# HuMem_rev_A.net
KiCad netlist of a schematic drawn in EAGLE
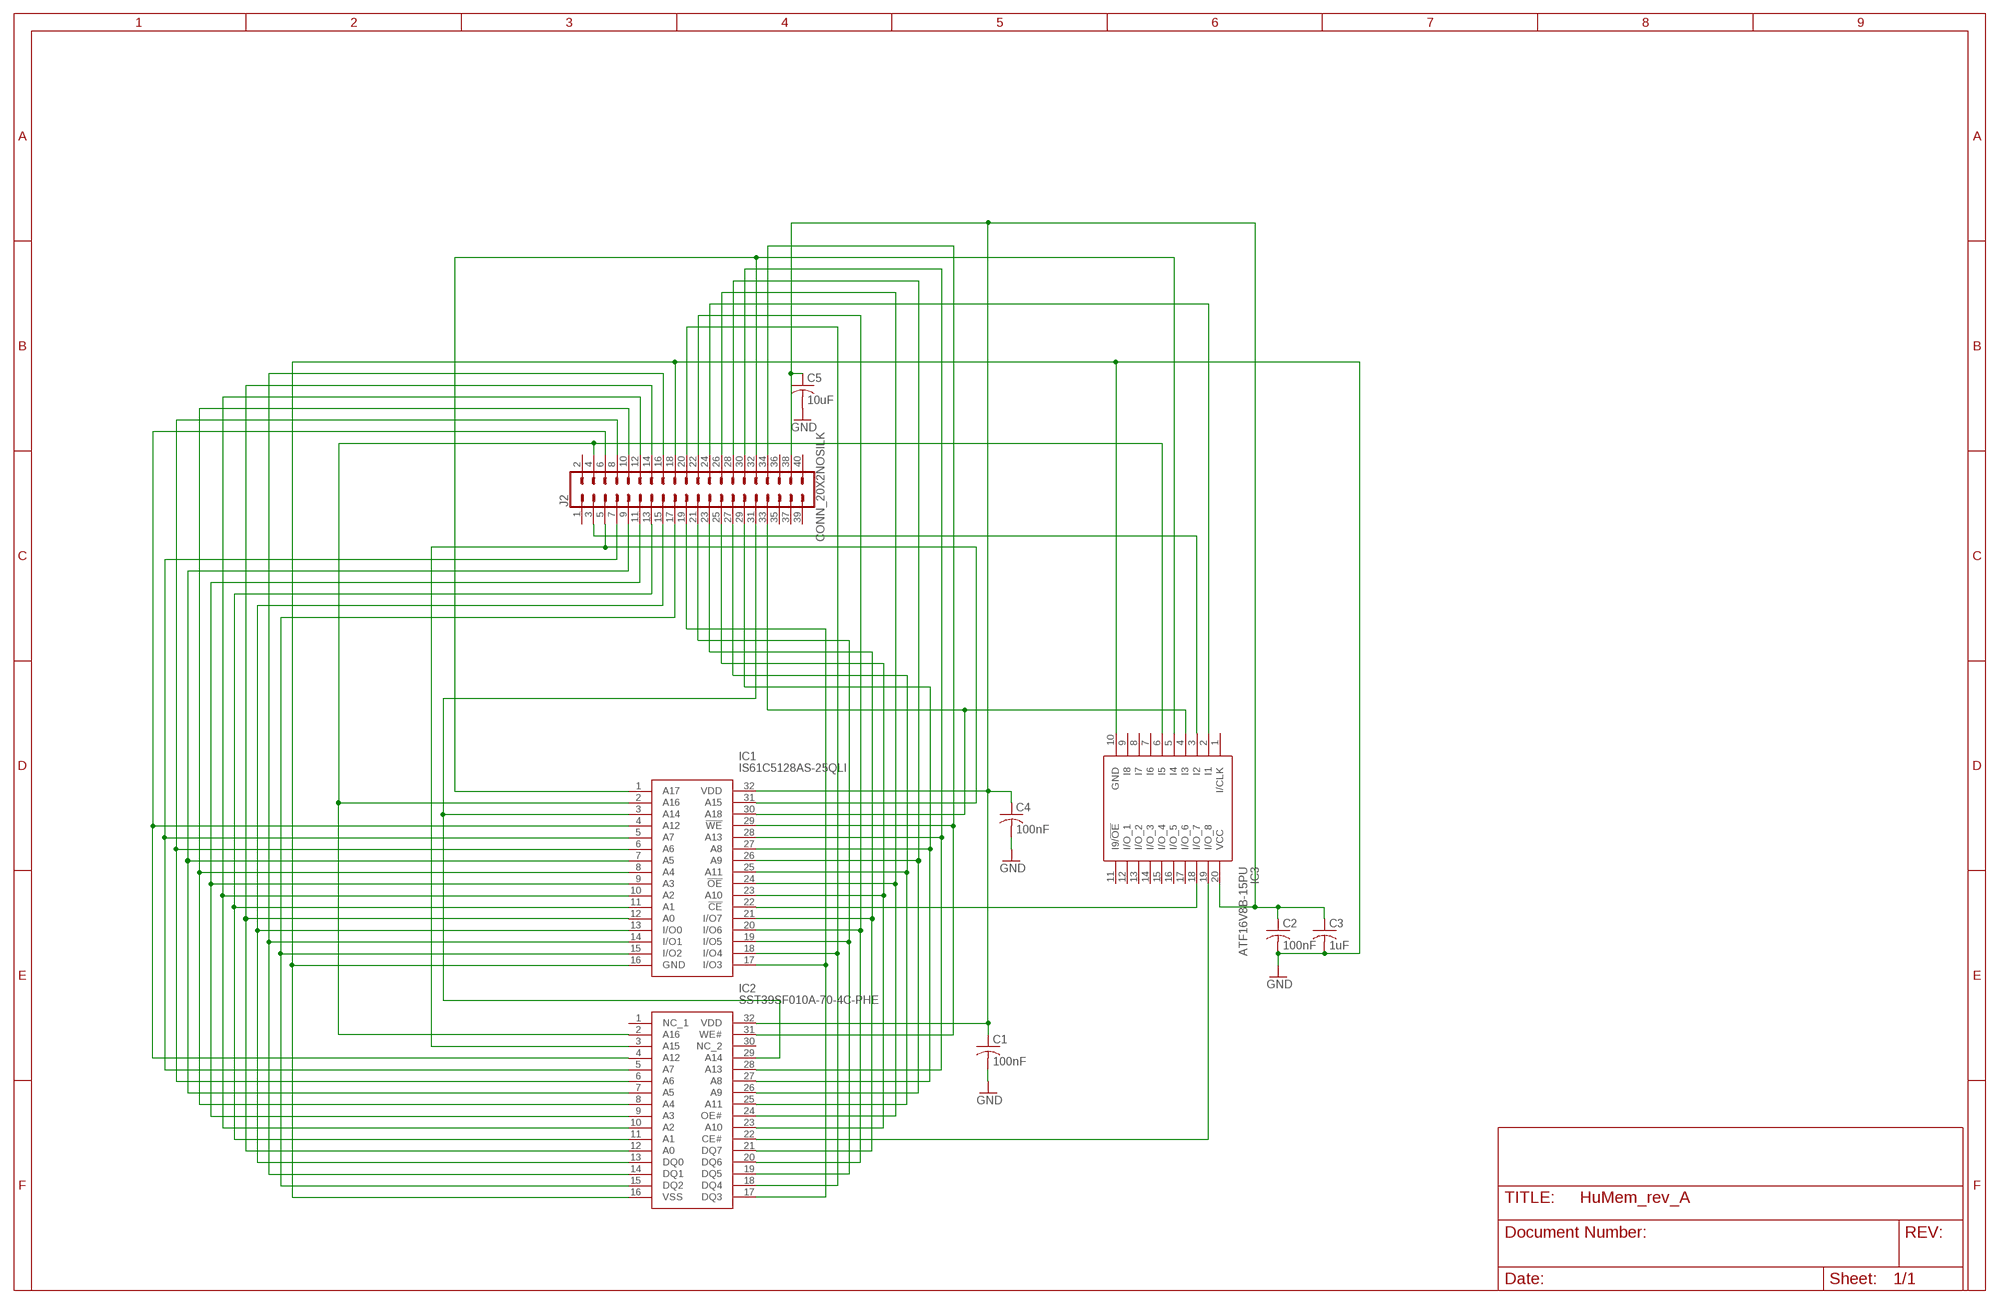
[diagram p0: schematic, sheet 1]

(export (version "E")
  (design (tool "Eeschema 10.0.6"))
  (components
    (comp (ref "C1")
      (value "100nF")
      (footprint "eagle-import:C0603")
      (libsource (lib "eagle-import") (part "C-USC0603"))
    )
    (comp (ref "C2")
      (value "100nF")
      (footprint "eagle-import:C0603")
      (libsource (lib "eagle-import") (part "C-USC0603"))
    )
    (comp (ref "C3")
      (value "1uF")
      (footprint "eagle-import:C0603")
      (libsource (lib "eagle-import") (part "C-USC0603"))
    )
    (comp (ref "C4")
      (value "100nF")
      (footprint "eagle-import:C0603")
      (libsource (lib "eagle-import") (part "C-USC0603"))
    )
    (comp (ref "C5")
      (value "10uF")
      (footprint "eagle-import:C0805")
      (libsource (lib "eagle-import") (part "C-USC0805"))
    )
    (comp (ref "IC1")
      (value "IS61C5128AS-25QLI")
      (footprint "eagle-import:SOIC127P1412X305-32N")
      (fields (field (name "MOUSER_PART_NUMBER") "870-61C5128AS-25QLI"))
      (libsource (lib "eagle-import") (part "IS61C5128AS-25QLI"))
    )
    (comp (ref "IC2")
      (value "SST39SF010A-70-4C-PHE")
      (footprint "eagle-import:DIP1556W56P254L4191H508Q32N")
      (fields (field (name "MOUSER_PART_NUMBER") "804-39SF010A7CPHE"))
      (libsource (lib "eagle-import") (part "SST39SF010A-70-4C-PHE"))
    )
    (comp (ref "IC3")
      (value "ATF16V8B-15PU")
      (footprint "eagle-import:DIP794W59P254L2591H533Q20N")
      (fields (field (name "MOUSER_PART_NUMBER") "556-AF16V8B15PU"))
      (libsource (lib "eagle-import") (part "ATF16V8B-15PU"))
    )
    (comp (ref "J2")
      (value "CONN_20X2NOSILK")
      (footprint "eagle-import:2X20_NOSILK")
      (libsource (lib "eagle-import") (part "CONN_20X2NOSILK"))
    )
  )
  (nets
    (net (code "1") (name "GND") (class "Default")
      (node (ref "C1") (pin "2") (pinfunction "2_2") (pintype "passive"))
      (node (ref "C2") (pin "2") (pinfunction "2_2") (pintype "passive"))
      (node (ref "C3") (pin "2") (pinfunction "2_2") (pintype "passive"))
      (node (ref "C4") (pin "2") (pinfunction "2_2") (pintype "passive"))
      (node (ref "C5") (pin "2") (pinfunction "2_2") (pintype "passive"))
      (node (ref "IC1") (pin "16") (pinfunction "GND_16") (pintype "bidirectional"))
      (node (ref "IC2") (pin "16") (pinfunction "VSS_16") (pintype "bidirectional"))
      (node (ref "IC3") (pin "10") (pinfunction "GND_10") (pintype "bidirectional"))
      (node (ref "J2") (pin "18") (pinfunction "18_18") (pintype "passive"))
    )
    (net (code "2") (name "Net-(IC1-A0)") (class "Default")
      (node (ref "IC1") (pin "12") (pinfunction "A0_12") (pintype "bidirectional"))
      (node (ref "IC2") (pin "12") (pinfunction "A0_12") (pintype "bidirectional"))
      (node (ref "J2") (pin "14") (pinfunction "14_14") (pintype "passive"))
    )
    (net (code "3") (name "Net-(IC1-A1)") (class "Default")
      (node (ref "IC1") (pin "11") (pinfunction "A1_11") (pintype "bidirectional"))
      (node (ref "IC2") (pin "11") (pinfunction "A1_11") (pintype "bidirectional"))
      (node (ref "J2") (pin "13") (pinfunction "13_13") (pintype "passive"))
    )
    (net (code "4") (name "Net-(IC1-A2)") (class "Default")
      (node (ref "IC1") (pin "10") (pinfunction "A2_10") (pintype "bidirectional"))
      (node (ref "IC2") (pin "10") (pinfunction "A2_10") (pintype "bidirectional"))
      (node (ref "J2") (pin "12") (pinfunction "12_12") (pintype "passive"))
    )
    (net (code "5") (name "Net-(IC1-A3)") (class "Default")
      (node (ref "IC1") (pin "9") (pinfunction "A3_9") (pintype "bidirectional"))
      (node (ref "IC2") (pin "9") (pinfunction "A3_9") (pintype "bidirectional"))
      (node (ref "J2") (pin "11") (pinfunction "11_11") (pintype "passive"))
    )
    (net (code "6") (name "Net-(IC1-A4)") (class "Default")
      (node (ref "IC1") (pin "8") (pinfunction "A4_8") (pintype "bidirectional"))
      (node (ref "IC2") (pin "8") (pinfunction "A4_8") (pintype "bidirectional"))
      (node (ref "J2") (pin "10") (pinfunction "10_10") (pintype "passive"))
    )
    (net (code "7") (name "Net-(IC1-A5)") (class "Default")
      (node (ref "IC1") (pin "7") (pinfunction "A5_7") (pintype "bidirectional"))
      (node (ref "IC2") (pin "7") (pinfunction "A5_7") (pintype "bidirectional"))
      (node (ref "J2") (pin "9") (pinfunction "9_9") (pintype "passive"))
    )
    (net (code "8") (name "Net-(IC1-A6)") (class "Default")
      (node (ref "IC1") (pin "6") (pinfunction "A6_6") (pintype "bidirectional"))
      (node (ref "IC2") (pin "6") (pinfunction "A6_6") (pintype "bidirectional"))
      (node (ref "J2") (pin "8") (pinfunction "8_8") (pintype "passive"))
    )
    (net (code "9") (name "Net-(IC1-A7)") (class "Default")
      (node (ref "IC1") (pin "5") (pinfunction "A7_5") (pintype "bidirectional"))
      (node (ref "IC2") (pin "5") (pinfunction "A7_5") (pintype "bidirectional"))
      (node (ref "J2") (pin "7") (pinfunction "7_7") (pintype "passive"))
    )
    (net (code "10") (name "Net-(IC1-A8)") (class "Default")
      (node (ref "IC1") (pin "27") (pinfunction "A8_27") (pintype "bidirectional"))
      (node (ref "IC2") (pin "27") (pinfunction "A8_27") (pintype "bidirectional"))
      (node (ref "J2") (pin "29") (pinfunction "29_29") (pintype "passive"))
    )
    (net (code "11") (name "Net-(IC1-A9)") (class "Default")
      (node (ref "IC1") (pin "26") (pinfunction "A9_26") (pintype "bidirectional"))
      (node (ref "IC2") (pin "26") (pinfunction "A9_26") (pintype "bidirectional"))
      (node (ref "J2") (pin "28") (pinfunction "28_28") (pintype "passive"))
    )
    (net (code "12") (name "Net-(IC1-A10)") (class "Default")
      (node (ref "IC1") (pin "23") (pinfunction "A10_23") (pintype "bidirectional"))
      (node (ref "IC2") (pin "23") (pinfunction "A10_23") (pintype "bidirectional"))
      (node (ref "J2") (pin "25") (pinfunction "25_25") (pintype "passive"))
    )
    (net (code "13") (name "Net-(IC1-A11)") (class "Default")
      (node (ref "IC1") (pin "25") (pinfunction "A11_25") (pintype "bidirectional"))
      (node (ref "IC2") (pin "25") (pinfunction "A11_25") (pintype "bidirectional"))
      (node (ref "J2") (pin "27") (pinfunction "27_27") (pintype "passive"))
    )
    (net (code "14") (name "Net-(IC1-A12)") (class "Default")
      (node (ref "IC1") (pin "4") (pinfunction "A12_4") (pintype "bidirectional"))
      (node (ref "IC2") (pin "4") (pinfunction "A12_4") (pintype "bidirectional"))
      (node (ref "J2") (pin "6") (pinfunction "6_6") (pintype "passive"))
    )
    (net (code "15") (name "Net-(IC1-A13)") (class "Default")
      (node (ref "IC1") (pin "28") (pinfunction "A13_28") (pintype "bidirectional"))
      (node (ref "IC2") (pin "28") (pinfunction "A13_28") (pintype "bidirectional"))
      (node (ref "J2") (pin "30") (pinfunction "30_30") (pintype "passive"))
    )
    (net (code "16") (name "Net-(IC1-A14)") (class "Default")
      (node (ref "IC1") (pin "3") (pinfunction "A14_3") (pintype "bidirectional"))
      (node (ref "IC2") (pin "29") (pinfunction "A14_29") (pintype "bidirectional"))
      (node (ref "J2") (pin "31") (pinfunction "31_31") (pintype "passive"))
    )
    (net (code "17") (name "Net-(IC1-A15)") (class "Default")
      (node (ref "IC1") (pin "31") (pinfunction "A15_31") (pintype "bidirectional"))
      (node (ref "IC2") (pin "3") (pinfunction "A15_3") (pintype "bidirectional"))
      (node (ref "J2") (pin "5") (pinfunction "5_5") (pintype "passive"))
    )
    (net (code "18") (name "Net-(IC1-A16)") (class "Default")
      (node (ref "IC1") (pin "2") (pinfunction "A16_2") (pintype "bidirectional"))
      (node (ref "IC2") (pin "2") (pinfunction "A16_2") (pintype "bidirectional"))
      (node (ref "IC3") (pin "6") (pinfunction "I5_6") (pintype "bidirectional"))
      (node (ref "J2") (pin "4") (pinfunction "4_4") (pintype "passive"))
    )
    (net (code "19") (name "Net-(IC1-A17)") (class "Default")
      (node (ref "IC1") (pin "1") (pinfunction "A17_1") (pintype "bidirectional"))
      (node (ref "IC3") (pin "5") (pinfunction "I4_5") (pintype "bidirectional"))
      (node (ref "J2") (pin "32") (pinfunction "32_32") (pintype "passive"))
    )
    (net (code "20") (name "Net-(IC1-A18)") (class "Default")
      (node (ref "IC1") (pin "30") (pinfunction "A18_30") (pintype "bidirectional"))
      (node (ref "IC3") (pin "4") (pinfunction "I3_4") (pintype "bidirectional"))
      (node (ref "J2") (pin "33") (pinfunction "33_33") (pintype "passive"))
    )
    (net (code "21") (name "Net-(IC1-I{slash}O0)") (class "Default")
      (node (ref "IC1") (pin "13") (pinfunction "I/O0_13") (pintype "bidirectional"))
      (node (ref "IC2") (pin "13") (pinfunction "DQ0_13") (pintype "bidirectional"))
      (node (ref "J2") (pin "15") (pinfunction "15_15") (pintype "passive"))
    )
    (net (code "22") (name "Net-(IC1-I{slash}O1)") (class "Default")
      (node (ref "IC1") (pin "14") (pinfunction "I/O1_14") (pintype "bidirectional"))
      (node (ref "IC2") (pin "14") (pinfunction "DQ1_14") (pintype "bidirectional"))
      (node (ref "J2") (pin "16") (pinfunction "16_16") (pintype "passive"))
    )
    (net (code "23") (name "Net-(IC1-I{slash}O2)") (class "Default")
      (node (ref "IC1") (pin "15") (pinfunction "I/O2_15") (pintype "bidirectional"))
      (node (ref "IC2") (pin "15") (pinfunction "DQ2_15") (pintype "bidirectional"))
      (node (ref "J2") (pin "17") (pinfunction "17_17") (pintype "passive"))
    )
    (net (code "24") (name "Net-(IC1-I{slash}O3)") (class "Default")
      (node (ref "IC1") (pin "17") (pinfunction "I/O3_17") (pintype "bidirectional"))
      (node (ref "IC2") (pin "17") (pinfunction "DQ3_17") (pintype "bidirectional"))
      (node (ref "J2") (pin "19") (pinfunction "19_19") (pintype "passive"))
    )
    (net (code "25") (name "Net-(IC1-I{slash}O4)") (class "Default")
      (node (ref "IC1") (pin "18") (pinfunction "I/O4_18") (pintype "bidirectional"))
      (node (ref "IC2") (pin "18") (pinfunction "DQ4_18") (pintype "bidirectional"))
      (node (ref "J2") (pin "20") (pinfunction "20_20") (pintype "passive"))
    )
    (net (code "26") (name "Net-(IC1-I{slash}O5)") (class "Default")
      (node (ref "IC1") (pin "19") (pinfunction "I/O5_19") (pintype "bidirectional"))
      (node (ref "IC2") (pin "19") (pinfunction "DQ5_19") (pintype "bidirectional"))
      (node (ref "J2") (pin "21") (pinfunction "21_21") (pintype "passive"))
    )
    (net (code "27") (name "Net-(IC1-I{slash}O6)") (class "Default")
      (node (ref "IC1") (pin "20") (pinfunction "I/O6_20") (pintype "bidirectional"))
      (node (ref "IC2") (pin "20") (pinfunction "DQ6_20") (pintype "bidirectional"))
      (node (ref "J2") (pin "22") (pinfunction "22_22") (pintype "passive"))
    )
    (net (code "28") (name "Net-(IC1-I{slash}O7)") (class "Default")
      (node (ref "IC1") (pin "21") (pinfunction "I/O7_21") (pintype "bidirectional"))
      (node (ref "IC2") (pin "21") (pinfunction "DQ7_21") (pintype "bidirectional"))
      (node (ref "J2") (pin "23") (pinfunction "23_23") (pintype "passive"))
    )
    (net (code "29") (name "Net-(IC1-VDD)") (class "Default")
      (node (ref "C1") (pin "1") (pinfunction "1_1") (pintype "passive"))
      (node (ref "C2") (pin "1") (pinfunction "1_1") (pintype "passive"))
      (node (ref "C3") (pin "1") (pinfunction "1_1") (pintype "passive"))
      (node (ref "C4") (pin "1") (pinfunction "1_1") (pintype "passive"))
      (node (ref "C5") (pin "1") (pinfunction "1_1") (pintype "passive"))
      (node (ref "IC1") (pin "32") (pinfunction "VDD_32") (pintype "bidirectional"))
      (node (ref "IC2") (pin "32") (pinfunction "VDD_32") (pintype "bidirectional"))
      (node (ref "IC3") (pin "20") (pinfunction "VCC_20") (pintype "bidirectional"))
      (node (ref "J2") (pin "38") (pinfunction "38_38") (pintype "passive"))
    )
    (net (code "30") (name "Net-(IC1-~{CE})") (class "Default")
      (node (ref "IC1") (pin "22") (pinfunction "~{CE}_22") (pintype "bidirectional"))
      (node (ref "IC3") (pin "18") (pinfunction "I/O_7_18") (pintype "bidirectional"))
    )
    (net (code "31") (name "Net-(IC1-~{OE})") (class "Default")
      (node (ref "IC1") (pin "24") (pinfunction "~{OE}_24") (pintype "bidirectional"))
      (node (ref "IC2") (pin "24") (pinfunction "OE#_24") (pintype "bidirectional"))
      (node (ref "J2") (pin "26") (pinfunction "26_26") (pintype "passive"))
    )
    (net (code "32") (name "Net-(IC1-~{WE})") (class "Default")
      (node (ref "IC1") (pin "29") (pinfunction "~{WE}_29") (pintype "bidirectional"))
      (node (ref "IC2") (pin "31") (pinfunction "WE#_31") (pintype "bidirectional"))
      (node (ref "J2") (pin "34") (pinfunction "34_34") (pintype "passive"))
    )
    (net (code "33") (name "Net-(IC2-CE#)") (class "Default")
      (node (ref "IC2") (pin "22") (pinfunction "CE#_22") (pintype "bidirectional"))
      (node (ref "IC3") (pin "19") (pinfunction "I/O_8_19") (pintype "bidirectional"))
    )
    (net (code "34") (name "Net-(IC3-I1)") (class "Default")
      (node (ref "IC3") (pin "2") (pinfunction "I1_2") (pintype "bidirectional"))
      (node (ref "J2") (pin "24") (pinfunction "24_24") (pintype "passive"))
    )
    (net (code "35") (name "Net-(IC3-I2)") (class "Default")
      (node (ref "IC3") (pin "3") (pinfunction "I2_3") (pintype "bidirectional"))
      (node (ref "J2") (pin "3") (pinfunction "3_3") (pintype "passive"))
    )
    (net (code "36") (name "unconnected-(IC2-NC_1-Pad1)") (class "Default")
      (node (ref "IC2") (pin "1") (pinfunction "NC_1_1") (pintype "bidirectional"))
    )
    (net (code "37") (name "unconnected-(IC2-NC_2-Pad30)") (class "Default")
      (node (ref "IC2") (pin "30") (pinfunction "NC_2_30") (pintype "bidirectional"))
    )
    (net (code "38") (name "unconnected-(IC3-I6-Pad7)") (class "Default")
      (node (ref "IC3") (pin "7") (pinfunction "I6_7") (pintype "bidirectional"))
    )
    (net (code "39") (name "unconnected-(IC3-I7-Pad8)") (class "Default")
      (node (ref "IC3") (pin "8") (pinfunction "I7_8") (pintype "bidirectional"))
    )
    (net (code "40") (name "unconnected-(IC3-I8-Pad9)") (class "Default")
      (node (ref "IC3") (pin "9") (pinfunction "I8_9") (pintype "bidirectional"))
    )
    (net (code "41") (name "unconnected-(IC3-I9{slash}~{OE}-Pad11)") (class "Default")
      (node (ref "IC3") (pin "11") (pinfunction "I9/~{OE}_11") (pintype "bidirectional"))
    )
    (net (code "42") (name "unconnected-(IC3-I{slash}CLK-Pad1)") (class "Default")
      (node (ref "IC3") (pin "1") (pinfunction "I/CLK_1") (pintype "bidirectional"))
    )
    (net (code "43") (name "unconnected-(IC3-I{slash}O_1-Pad12)") (class "Default")
      (node (ref "IC3") (pin "12") (pinfunction "I/O_1_12") (pintype "bidirectional"))
    )
    (net (code "44") (name "unconnected-(IC3-I{slash}O_2-Pad13)") (class "Default")
      (node (ref "IC3") (pin "13") (pinfunction "I/O_2_13") (pintype "bidirectional"))
    )
    (net (code "45") (name "unconnected-(IC3-I{slash}O_3-Pad14)") (class "Default")
      (node (ref "IC3") (pin "14") (pinfunction "I/O_3_14") (pintype "bidirectional"))
    )
    (net (code "46") (name "unconnected-(IC3-I{slash}O_4-Pad15)") (class "Default")
      (node (ref "IC3") (pin "15") (pinfunction "I/O_4_15") (pintype "bidirectional"))
    )
    (net (code "47") (name "unconnected-(IC3-I{slash}O_5-Pad16)") (class "Default")
      (node (ref "IC3") (pin "16") (pinfunction "I/O_5_16") (pintype "bidirectional"))
    )
    (net (code "48") (name "unconnected-(IC3-I{slash}O_6-Pad17)") (class "Default")
      (node (ref "IC3") (pin "17") (pinfunction "I/O_6_17") (pintype "bidirectional"))
    )
    (net (code "49") (name "unconnected-(J2-Pad1)") (class "Default")
      (node (ref "J2") (pin "1") (pinfunction "1_1") (pintype "passive"))
    )
    (net (code "50") (name "unconnected-(J2-Pad2)") (class "Default")
      (node (ref "J2") (pin "2") (pinfunction "2_2") (pintype "passive"))
    )
    (net (code "51") (name "unconnected-(J2-Pad35)") (class "Default")
      (node (ref "J2") (pin "35") (pinfunction "35_35") (pintype "passive"))
    )
    (net (code "52") (name "unconnected-(J2-Pad36)") (class "Default")
      (node (ref "J2") (pin "36") (pinfunction "36_36") (pintype "passive"))
    )
    (net (code "53") (name "unconnected-(J2-Pad37)") (class "Default")
      (node (ref "J2") (pin "37") (pinfunction "37_37") (pintype "passive"))
    )
    (net (code "54") (name "unconnected-(J2-Pad39)") (class "Default")
      (node (ref "J2") (pin "39") (pinfunction "39_39") (pintype "passive"))
    )
    (net (code "55") (name "unconnected-(J2-Pad40)") (class "Default")
      (node (ref "J2") (pin "40") (pinfunction "40_40") (pintype "passive"))
    )
  )
)
